# SCH_Satlla_4_Back_side_2023-01-29.net
KiCad netlist of a schematic drawn in EasyEDA
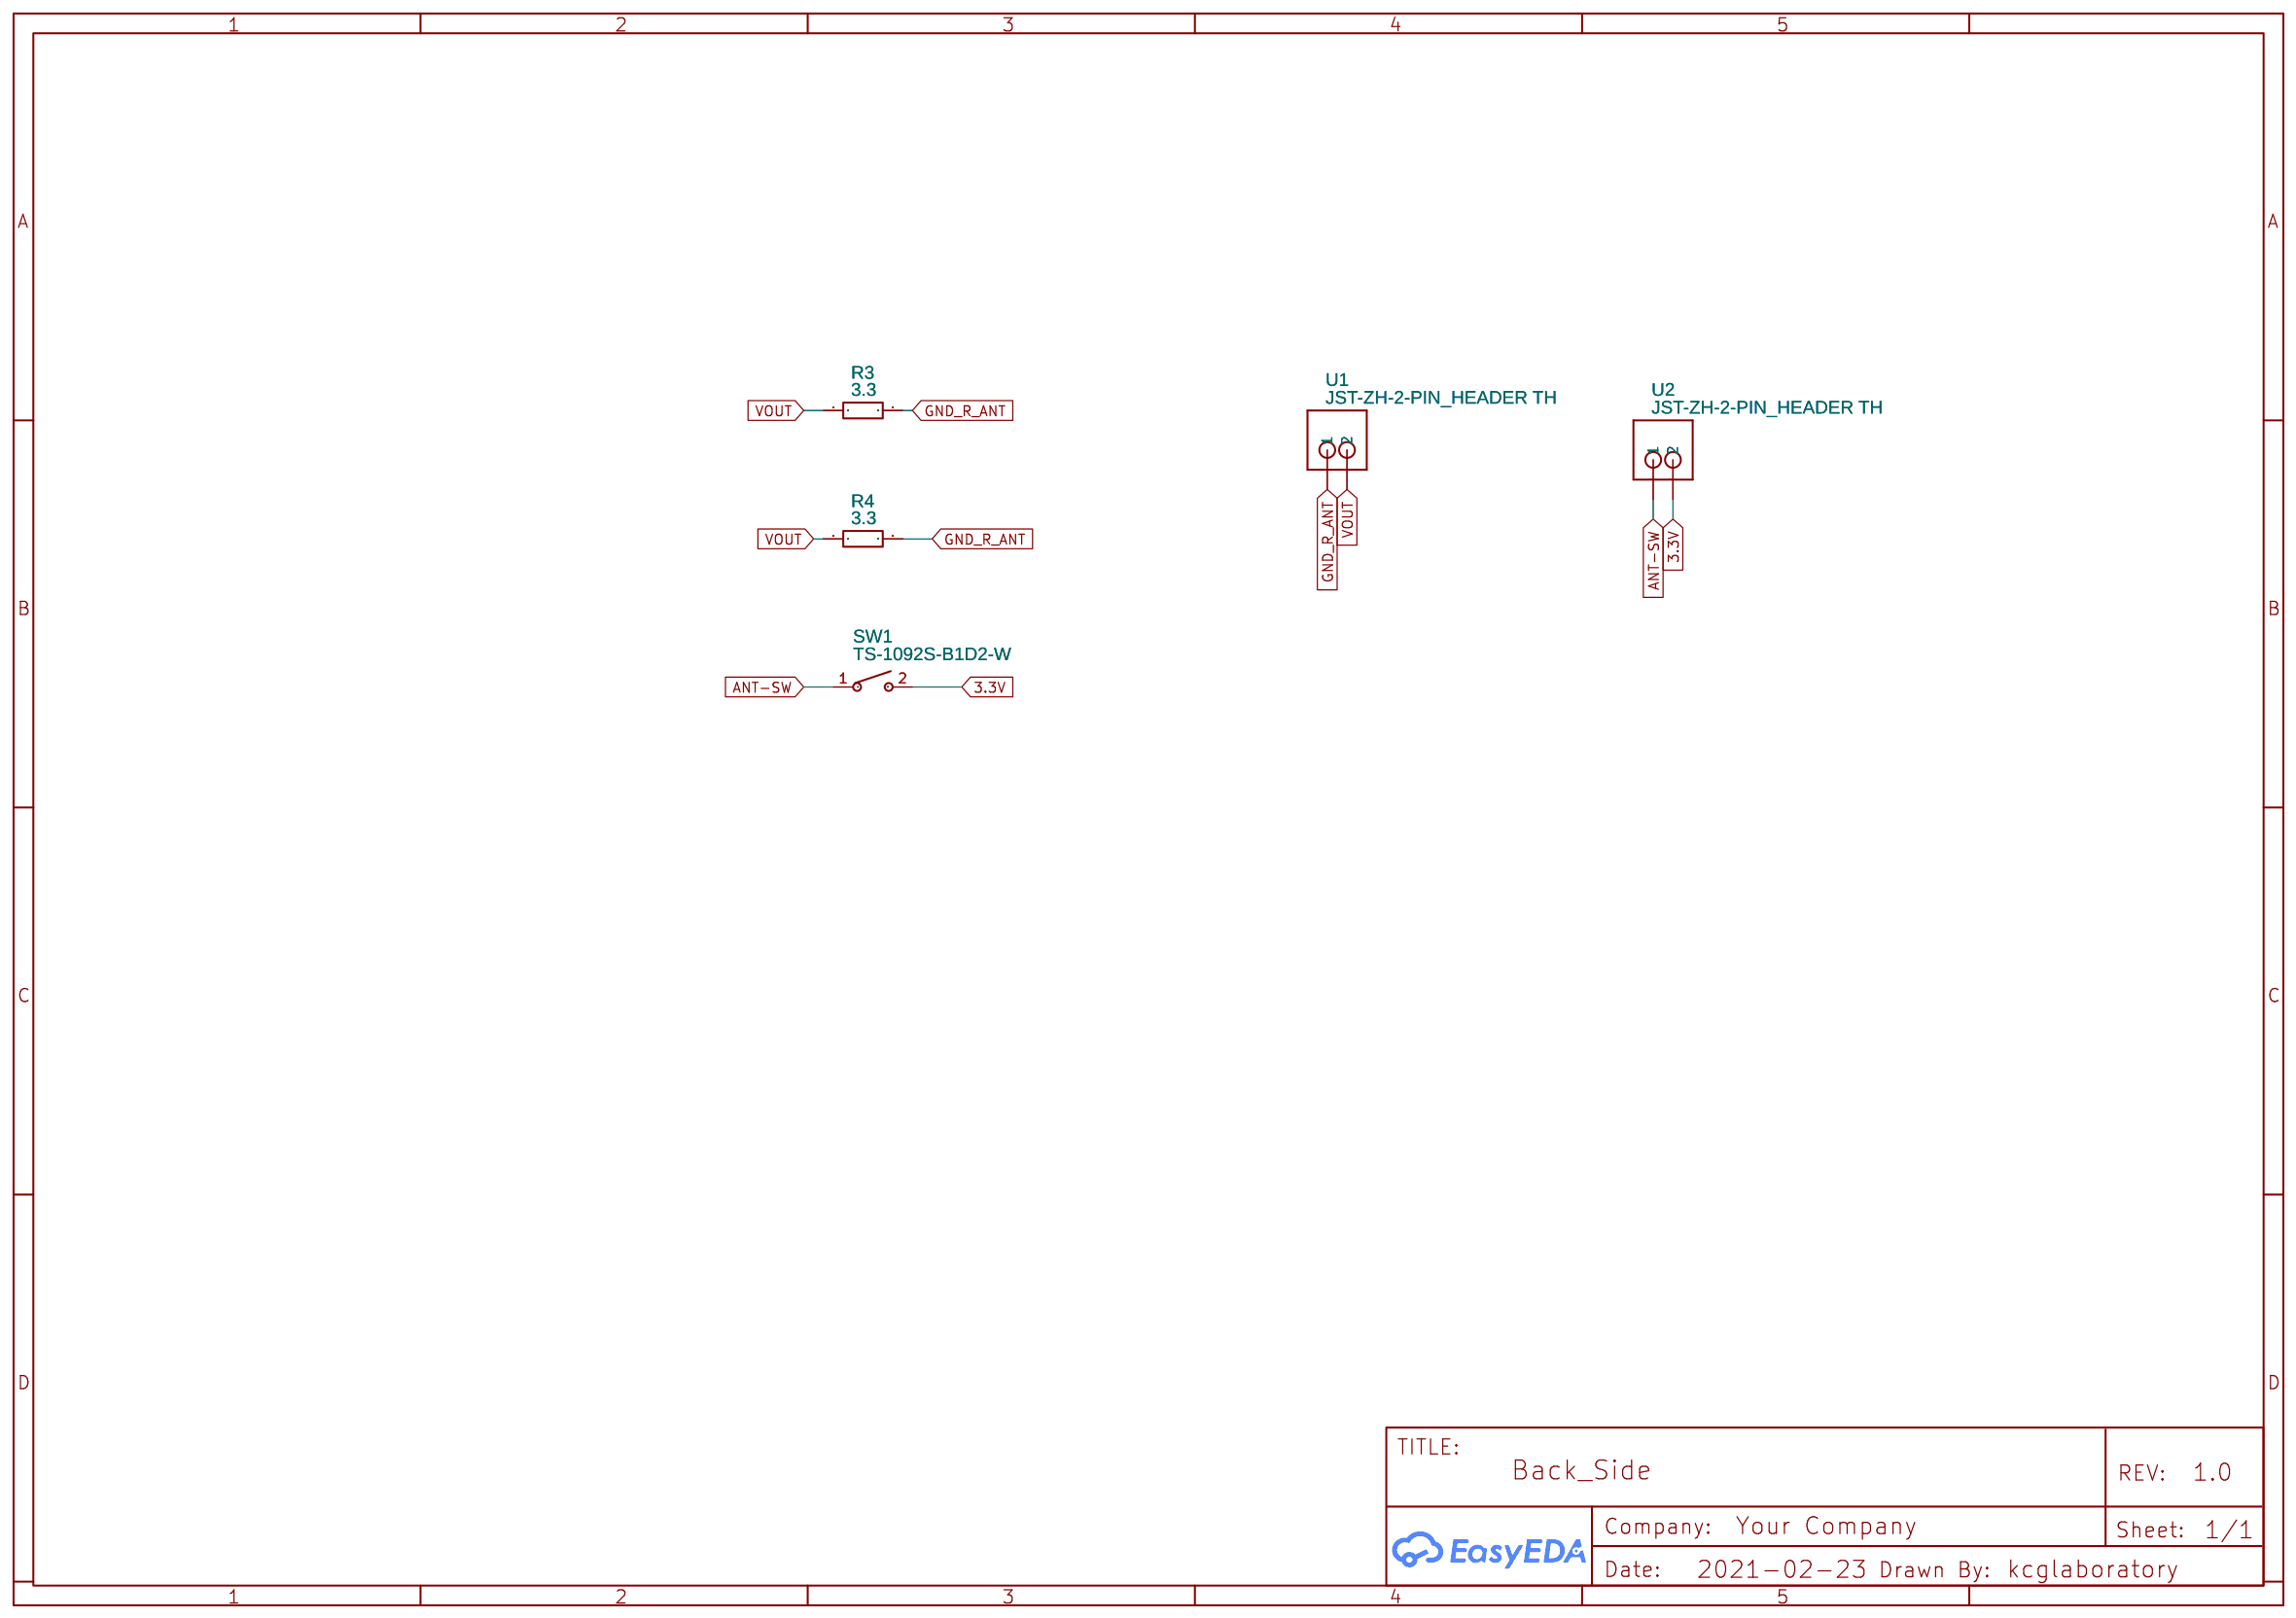
[diagram p0: schematic sheet]

(export (version "E")
  (design (tool "Eeschema 10.0.6"))
  (components
    (comp (ref "R3")
      (value "3.3")
      (fields
        (field (name "BOM_Manufacturer Part") "RD50T53R3J")
        (field (name "BOM_Supplier Part") "C167570")
      )
      (libsource (lib "") (part "RD50T53R3J"))
    )
    (comp (ref "R4")
      (value "3.3")
      (fields
        (field (name "BOM_Manufacturer Part") "RD50T53R3J")
        (field (name "BOM_Supplier Part") "C167570")
      )
      (libsource (lib "") (part "RD50T53R3J"))
    )
    (comp (ref "SW1")
      (value "TS-1092S-B1D2-W")
      (fields (field (name "BOM_Supplier Part") "C782859"))
      (libsource (lib "") (part "TS-1092S-B1D2-W"))
    )
    (comp (ref "U1") (value "JST-ZH-2-PIN_HEADER TH") (libsource (lib "") (part "JST-ZH-2-PIN_HEADER TH")))
    (comp (ref "U2") (value "JST-ZH-2-PIN_HEADER TH") (libsource (lib "") (part "JST-ZH-2-PIN_HEADER TH")))
  )
  (nets
    (net (code "1") (name "3.3V") (class "Default")
      (node (ref "SW1") (pin "2") (pinfunction "2_2") (pintype "unspecified"))
      (node (ref "U2") (pin "2") (pinfunction "2_2") (pintype "unspecified"))
    )
    (net (code "2") (name "ANT-SW") (class "Default")
      (node (ref "SW1") (pin "1") (pinfunction "1_1") (pintype "unspecified"))
      (node (ref "U2") (pin "1") (pinfunction "1_1") (pintype "unspecified"))
    )
    (net (code "3") (name "GND_R_ANT") (class "Default")
      (node (ref "R3") (pin "2") (pinfunction "2_2") (pintype "unspecified"))
      (node (ref "R4") (pin "2") (pinfunction "2_2") (pintype "unspecified"))
      (node (ref "U1") (pin "1") (pinfunction "1_1") (pintype "unspecified"))
    )
    (net (code "4") (name "VOUT") (class "Default")
      (node (ref "R3") (pin "1") (pinfunction "1_1") (pintype "unspecified"))
      (node (ref "R4") (pin "1") (pinfunction "1_1") (pintype "unspecified"))
      (node (ref "U1") (pin "2") (pinfunction "2_2") (pintype "unspecified"))
    )
  )
)
